# led.net
KiCad netlist of a schematic drawn in EAGLE
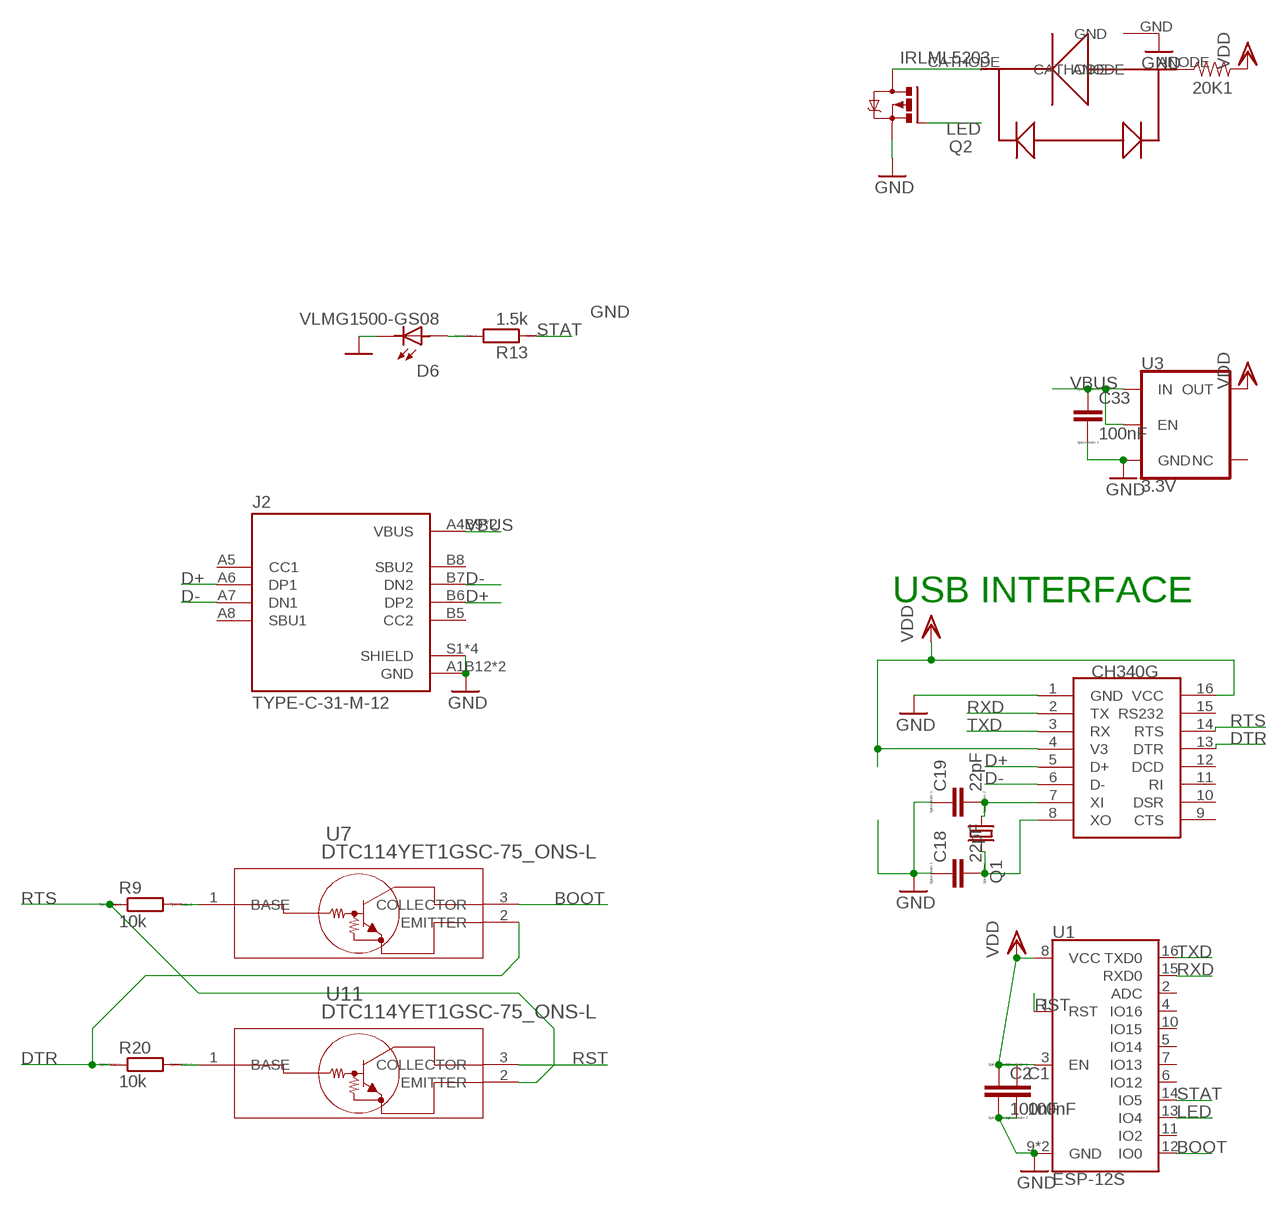
[diagram p0: schematic, sheet 1]

(export (version "E")
  (design (tool "Eeschema 10.0.6"))
  (components
    (comp (ref "20K1")
      (value "0.05")
      (footprint "eagle-import:1210")
      (libsource (lib "eagle-import") (part "0.1OHM-1210-1/2W-1%"))
    )
    (comp (ref "C1")
      (value "100nF")
      (footprint "eagle-import:C0402")
      (libsource (lib "eagle-import") (part "CC0402"))
    )
    (comp (ref "C2")
      (value "100nF")
      (footprint "eagle-import:C0402")
      (libsource (lib "eagle-import") (part "CC0402"))
    )
    (comp (ref "C18")
      (value "22pF")
      (footprint "eagle-import:C0402")
      (libsource (lib "eagle-import") (part "CC0402"))
    )
    (comp (ref "C19")
      (value "22pF")
      (footprint "eagle-import:C0402")
      (libsource (lib "eagle-import") (part "CC0402"))
    )
    (comp (ref "C33")
      (value "100nF")
      (footprint "eagle-import:C0402")
      (libsource (lib "eagle-import") (part "CC0402"))
    )
    (comp (ref "D6")
      (value "VLMG1500-GS08")
      (footprint "eagle-import:LEDC1005X35N")
      (fields (field (name "MF") "Vishay"))
      (libsource (lib "eagle-import") (part "VLMG1500-GS08"))
    )
    (comp (ref "J2")
      (value "TYPE-C-31-M-12")
      (footprint "eagle-import:HRO_TYPE-C-31-M-12")
      (fields (field (name "MF") "HRO Electronics Co., Ltd."))
      (libsource (lib "eagle-import") (part "TYPE-C-31-M-12"))
    )
    (comp (ref "Q1")
      (value "KX-7")
      (footprint "eagle-import:3.2X2.5_KX-7")
      (libsource (lib "eagle-import") (part "KX-7"))
    )
    (comp (ref "Q2")
      (value "IRLML5203")
      (footprint "eagle-import:MICRO3")
      (libsource (lib "eagle-import") (part "IRLML5203"))
    )
    (comp (ref "R9")
      (value "10k")
      (footprint "eagle-import:R0402")
      (libsource (lib "eagle-import") (part "RR0402"))
    )
    (comp (ref "R13")
      (value "1.5k")
      (footprint "eagle-import:R0402")
      (libsource (lib "eagle-import") (part "RR0402"))
    )
    (comp (ref "R20")
      (value "10k")
      (footprint "eagle-import:R0402")
      (libsource (lib "eagle-import") (part "RR0402"))
    )
    (comp (ref "U$1")
      (value "ELSW(1W)")
      (footprint "eagle-import:ELSW(1W)")
      (libsource (lib "eagle-import") (part "ELSW(1W)"))
    )
    (comp (ref "U1")
      (value "ESP-12S")
      (footprint "eagle-import:ESP-12S")
      (fields (field (name "MF") "RF Solutions"))
      (libsource (lib "eagle-import") (part "ESP-12S"))
    )
    (comp (ref "U3")
      (value "3.3V")
      (footprint "eagle-import:SOT23-5")
      (libsource (lib "eagle-import") (part "V_REG_AP2112K-3.3V"))
    )
    (comp (ref "U5")
      (value "H")
      (footprint "eagle-import:SOIC16")
      (libsource (lib "eagle-import") (part "CH340G"))
    )
    (comp (ref "U7")
      (value "DTC114YET1GSC-75_ONS-L")
      (footprint "eagle-import:SC-75_ONS-L")
      (fields
        (field (name "MANUFACTURER_PART_NUMBER") "DTC114YET1G")
        (field (name "COPYRIGHT") "Copyright (C) 2018 Accelerated Designs. All rights reserved")
      )
      (libsource (lib "eagle-import") (part "DTC114YET1GSC-75_ONS-L"))
    )
    (comp (ref "U11")
      (value "DTC114YET1GSC-75_ONS-L")
      (footprint "eagle-import:SC-75_ONS-L")
      (fields
        (field (name "MANUFACTURER_PART_NUMBER") "DTC114YET1G")
        (field (name "COPYRIGHT") "Copyright (C) 2018 Accelerated Designs. All rights reserved")
      )
      (libsource (lib "eagle-import") (part "DTC114YET1GSC-75_ONS-L"))
    )
  )
  (nets
    (net (code "1") (name "/BOOT") (class "Default")
      (node (ref "U1") (pin "12") (pinfunction "IO0_12") (pintype "bidirectional"))
      (node (ref "U7") (pin "3") (pinfunction "COLLECTOR_3") (pintype "output"))
    )
    (net (code "2") (name "/D+") (class "Default")
      (node (ref "J2") (pin "A6") (pinfunction "DP1_A6") (pintype "bidirectional"))
      (node (ref "J2") (pin "B6") (pinfunction "DP2_B6") (pintype "bidirectional"))
      (node (ref "U5") (pin "5") (pinfunction "D+_5") (pintype "bidirectional"))
    )
    (net (code "3") (name "/D-") (class "Default")
      (node (ref "J2") (pin "A7") (pinfunction "DN1_A7") (pintype "bidirectional"))
      (node (ref "J2") (pin "B7") (pinfunction "DN2_B7") (pintype "bidirectional"))
      (node (ref "U5") (pin "6") (pinfunction "D-_6") (pintype "bidirectional"))
    )
    (net (code "4") (name "/DTR") (class "Default")
      (node (ref "R20") (pin "1") (pinfunction "1_1") (pintype "passive"))
      (node (ref "U5") (pin "13") (pinfunction "DTR_13") (pintype "bidirectional"))
      (node (ref "U7") (pin "2") (pinfunction "EMITTER_2") (pintype "passive"))
    )
    (net (code "5") (name "/LED") (class "Default")
      (node (ref "Q2") (pin "1") (pinfunction "G_1") (pintype "passive"))
      (node (ref "U1") (pin "13") (pinfunction "IO4_13") (pintype "bidirectional"))
    )
    (net (code "6") (name "/RST") (class "Default")
      (node (ref "U1") (pin "1") (pinfunction "RST_1") (pintype "bidirectional"))
      (node (ref "U11") (pin "3") (pinfunction "COLLECTOR_3") (pintype "output"))
    )
    (net (code "7") (name "/RTS") (class "Default")
      (node (ref "R9") (pin "1") (pinfunction "1_1") (pintype "passive"))
      (node (ref "U11") (pin "2") (pinfunction "EMITTER_2") (pintype "passive"))
      (node (ref "U5") (pin "14") (pinfunction "RTS_14") (pintype "bidirectional"))
    )
    (net (code "8") (name "/RXD") (class "Default")
      (node (ref "U1") (pin "15") (pinfunction "RXD0_15") (pintype "bidirectional"))
      (node (ref "U5") (pin "2") (pinfunction "TX_2") (pintype "bidirectional"))
    )
    (net (code "9") (name "/STAT") (class "Default")
      (node (ref "R13") (pin "1") (pinfunction "1_1") (pintype "passive"))
      (node (ref "U1") (pin "14") (pinfunction "IO5_14") (pintype "bidirectional"))
    )
    (net (code "10") (name "/TXD") (class "Default")
      (node (ref "U1") (pin "16") (pinfunction "TXD0_16") (pintype "bidirectional"))
      (node (ref "U5") (pin "3") (pinfunction "RX_3") (pintype "bidirectional"))
    )
    (net (code "11") (name "/VBUS") (class "Default")
      (node (ref "C33") (pin "1") (pinfunction "1_1") (pintype "passive"))
      (node (ref "J2") (pin "A4B9") (pinfunction "VBUS_A4B9") (pintype "power_in"))
      (node (ref "J2") (pin "B4A9") (pinfunction "VBUS_B4A9") (pintype "power_in"))
      (node (ref "U3") (pin "1") (pinfunction "IN_1") (pintype "input"))
      (node (ref "U3") (pin "3") (pinfunction "EN_3") (pintype "input"))
    )
    (net (code "12") (name "GND") (class "Default")
      (node (ref "C1") (pin "2") (pinfunction "2_2") (pintype "passive"))
      (node (ref "C18") (pin "1") (pinfunction "1_1") (pintype "passive"))
      (node (ref "C19") (pin "1") (pinfunction "1_1") (pintype "passive"))
      (node (ref "C2") (pin "2") (pinfunction "2_2") (pintype "passive"))
      (node (ref "C33") (pin "2") (pinfunction "2_2") (pintype "passive"))
      (node (ref "D6") (pin "2") (pinfunction "2_2") (pintype "passive"))
      (node (ref "J2") (pin "A1B12") (pinfunction "GND_A1B12") (pintype "power_in"))
      (node (ref "J2") (pin "B1A12") (pinfunction "GND_B1A12") (pintype "power_in"))
      (node (ref "J2") (pin "S1") (pinfunction "SHIELD_S1") (pintype "passive"))
      (node (ref "J2") (pin "S2") (pinfunction "SHIELD_S2") (pintype "passive"))
      (node (ref "J2") (pin "S3") (pinfunction "SHIELD_S3") (pintype "passive"))
      (node (ref "J2") (pin "S4") (pinfunction "SHIELD_S4") (pintype "passive"))
      (node (ref "Q2") (pin "2") (pinfunction "S_2") (pintype "passive"))
      (node (ref "U$1") (pin "GND") (pinfunction "GND_GND") (pintype "bidirectional"))
      (node (ref "U1") (pin "9") (pinfunction "GND_9") (pintype "bidirectional"))
      (node (ref "U1") (pin "P$1") (pinfunction "GND_P$1") (pintype "bidirectional"))
      (node (ref "U3") (pin "2") (pinfunction "GND_2") (pintype "input"))
      (node (ref "U5") (pin "1") (pinfunction "GND_1") (pintype "bidirectional"))
    )
    (net (code "13") (name "Net-(20K1-Pad1)") (class "Default")
      (node (ref "20K1") (pin "1") (pinfunction "1_1") (pintype "passive"))
      (node (ref "U$1") (pin "ANODE") (pinfunction "ANODE_ANODE") (pintype "bidirectional"))
    )
    (net (code "14") (name "Net-(D6-Pad1)") (class "Default")
      (node (ref "D6") (pin "1") (pinfunction "1_1") (pintype "passive"))
      (node (ref "R13") (pin "2") (pinfunction "2_2") (pintype "passive"))
    )
    (net (code "15") (name "Net-(Q1-2)") (class "Default")
      (node (ref "C18") (pin "2") (pinfunction "2_2") (pintype "passive"))
      (node (ref "Q1") (pin "3") (pinfunction "2_3") (pintype "passive"))
      (node (ref "U5") (pin "8") (pinfunction "XO_8") (pintype "bidirectional"))
    )
    (net (code "16") (name "Net-(Q2-D)") (class "Default")
      (node (ref "Q2") (pin "3") (pinfunction "D_3") (pintype "passive"))
      (node (ref "U$1") (pin "CATHODE") (pinfunction "CATHODE_CATHODE") (pintype "bidirectional"))
    )
    (net (code "17") (name "Net-(U5-XI)") (class "Default")
      (node (ref "C19") (pin "2") (pinfunction "2_2") (pintype "passive"))
      (node (ref "Q1") (pin "1") (pinfunction "1_1") (pintype "passive"))
      (node (ref "U5") (pin "7") (pinfunction "XI_7") (pintype "bidirectional"))
    )
    (net (code "18") (name "Net-(U7-BASE)") (class "Default")
      (node (ref "R9") (pin "2") (pinfunction "2_2") (pintype "passive"))
      (node (ref "U7") (pin "1") (pinfunction "BASE_1") (pintype "input"))
    )
    (net (code "19") (name "Net-(U11-BASE)") (class "Default")
      (node (ref "R20") (pin "2") (pinfunction "2_2") (pintype "passive"))
      (node (ref "U11") (pin "1") (pinfunction "BASE_1") (pintype "input"))
    )
    (net (code "20") (name "VDD") (class "Default")
      (node (ref "20K1") (pin "2") (pinfunction "2_2") (pintype "passive"))
      (node (ref "C1") (pin "1") (pinfunction "1_1") (pintype "passive"))
      (node (ref "C2") (pin "1") (pinfunction "1_1") (pintype "passive"))
      (node (ref "U1") (pin "3") (pinfunction "EN_3") (pintype "bidirectional"))
      (node (ref "U1") (pin "8") (pinfunction "VCC_8") (pintype "bidirectional"))
      (node (ref "U3") (pin "5") (pinfunction "OUT_5") (pintype "passive"))
      (node (ref "U5") (pin "16") (pinfunction "VCC_16") (pintype "bidirectional"))
      (node (ref "U5") (pin "4") (pinfunction "V3_4") (pintype "bidirectional"))
    )
    (net (code "21") (name "unconnected-(J2-CC1-PadA5)") (class "Default")
      (node (ref "J2") (pin "A5") (pinfunction "CC1_A5") (pintype "bidirectional"))
    )
    (net (code "22") (name "unconnected-(J2-CC2-PadB5)") (class "Default")
      (node (ref "J2") (pin "B5") (pinfunction "CC2_B5") (pintype "bidirectional"))
    )
    (net (code "23") (name "unconnected-(J2-SBU1-PadA8)") (class "Default")
      (node (ref "J2") (pin "A8") (pinfunction "SBU1_A8") (pintype "bidirectional"))
    )
    (net (code "24") (name "unconnected-(J2-SBU2-PadB8)") (class "Default")
      (node (ref "J2") (pin "B8") (pinfunction "SBU2_B8") (pintype "bidirectional"))
    )
    (net (code "25") (name "unconnected-(U1-ADC-Pad2)") (class "Default")
      (node (ref "U1") (pin "2") (pinfunction "ADC_2") (pintype "bidirectional"))
    )
    (net (code "26") (name "unconnected-(U1-IO2-Pad11)") (class "Default")
      (node (ref "U1") (pin "11") (pinfunction "IO2_11") (pintype "bidirectional"))
    )
    (net (code "27") (name "unconnected-(U1-IO12-Pad6)") (class "Default")
      (node (ref "U1") (pin "6") (pinfunction "IO12_6") (pintype "bidirectional"))
    )
    (net (code "28") (name "unconnected-(U1-IO13-Pad7)") (class "Default")
      (node (ref "U1") (pin "7") (pinfunction "IO13_7") (pintype "bidirectional"))
    )
    (net (code "29") (name "unconnected-(U1-IO14-Pad5)") (class "Default")
      (node (ref "U1") (pin "5") (pinfunction "IO14_5") (pintype "bidirectional"))
    )
    (net (code "30") (name "unconnected-(U1-IO15-Pad10)") (class "Default")
      (node (ref "U1") (pin "10") (pinfunction "IO15_10") (pintype "bidirectional"))
    )
    (net (code "31") (name "unconnected-(U1-IO16-Pad4)") (class "Default")
      (node (ref "U1") (pin "4") (pinfunction "IO16_4") (pintype "bidirectional"))
    )
    (net (code "32") (name "unconnected-(U3-NC-Pad4)") (class "Default")
      (node (ref "U3") (pin "4") (pinfunction "NC_4") (pintype "no_connect"))
    )
    (net (code "33") (name "unconnected-(U5-CTS-Pad9)") (class "Default")
      (node (ref "U5") (pin "9") (pinfunction "CTS_9") (pintype "bidirectional"))
    )
    (net (code "34") (name "unconnected-(U5-DCD-Pad12)") (class "Default")
      (node (ref "U5") (pin "12") (pinfunction "DCD_12") (pintype "bidirectional"))
    )
    (net (code "35") (name "unconnected-(U5-DSR-Pad10)") (class "Default")
      (node (ref "U5") (pin "10") (pinfunction "DSR_10") (pintype "bidirectional"))
    )
    (net (code "36") (name "unconnected-(U5-RI-Pad11)") (class "Default")
      (node (ref "U5") (pin "11") (pinfunction "RI_11") (pintype "bidirectional"))
    )
    (net (code "37") (name "unconnected-(U5-RS232-Pad15)") (class "Default")
      (node (ref "U5") (pin "15") (pinfunction "RS232_15") (pintype "bidirectional"))
    )
  )
)
